# Sheet1.net
KiCad netlist of a schematic drawn in Altium Designer
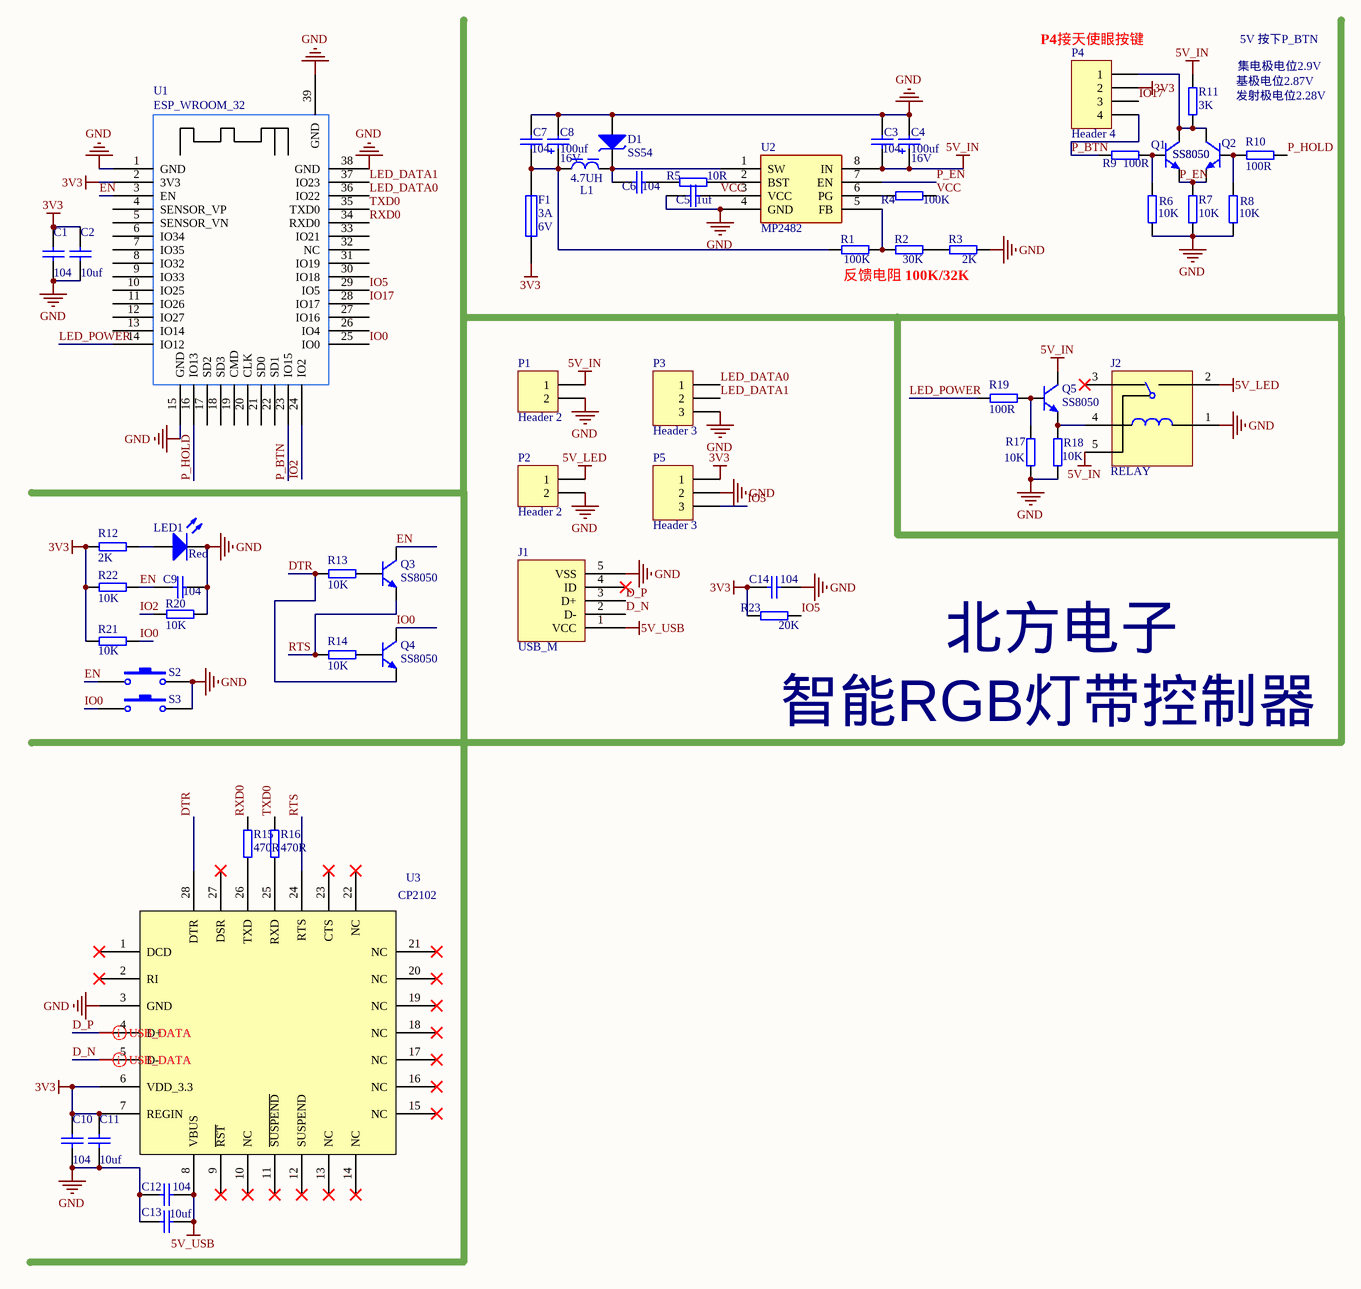
[diagram p0: Sheet1.SchDoc]

(export (version "E")
  (design (tool "Eeschema 10.0.6"))
  (components
    (comp (ref "C1")
      (value "104")
      (footprint "CAPC1005[0402]S")
      (description "Chip Capacitor, Silkscreen Border")
      (fields
        (field (name "VOLTAGE") "63V")
        (field (name "TOLERANCE") "Y5V")
        (field (name "PUBLISHER") "Altium Limited")
      )
      (libsource (lib "!)Miscellaneous Integrated Library") (part "Cap Chip 2"))
    )
    (comp (ref "C2")
      (value "10uf")
      (footprint "CAPC1005[0402]S")
      (description "Chip Capacitor, Silkscreen Border")
      (fields
        (field (name "VOLTAGE") "63V")
        (field (name "TOLERANCE") "Y5V")
        (field (name "PUBLISHER") "Altium Limited")
      )
      (libsource (lib "!)Miscellaneous Integrated Library") (part "Cap Chip 2"))
    )
    (comp (ref "C3")
      (value "104")
      (footprint "CAPC1005[0402]S")
      (description "Chip Capacitor, Silkscreen Border")
      (fields
        (field (name "VOLTAGE") "63V")
        (field (name "TOLERANCE") "Y5V")
        (field (name "PUBLISHER") "Altium Limited")
      )
      (libsource (lib "!)Miscellaneous Integrated Library") (part "Cap Chip 2"))
    )
    (comp (ref "C4")
      (value "100uf")
      (footprint "CAPT6032")
      (description "Molded (Tantalum) Capacitor, 2-Leads,")
      (fields (field (name "VOLTAGE") "16V") (field (name "PUBLISHER") "Altium Limited"))
      (libsource (lib "!)Miscellaneous Integrated Library") (part "Cap Tan"))
    )
    (comp (ref "C5")
      (value "1uf")
      (footprint "CAPC1005[0402]S")
      (description "Chip Capacitor, Silkscreen Border")
      (fields
        (field (name "VOLTAGE") "63V")
        (field (name "TOLERANCE") "Y5V")
        (field (name "PUBLISHER") "Altium Limited")
      )
      (libsource (lib "!)Miscellaneous Integrated Library") (part "Cap Chip 2"))
    )
    (comp (ref "C6")
      (value "104")
      (footprint "CAPC1005[0402]S")
      (description "Chip Capacitor, Silkscreen Border")
      (fields
        (field (name "VOLTAGE") "63V")
        (field (name "TOLERANCE") "Y5V")
        (field (name "PUBLISHER") "Altium Limited")
      )
      (libsource (lib "!)Miscellaneous Integrated Library") (part "Cap Chip 2"))
    )
    (comp (ref "C7")
      (value "104")
      (footprint "CAPC1005[0402]S")
      (description "Chip Capacitor, Silkscreen Border")
      (fields
        (field (name "VOLTAGE") "63V")
        (field (name "TOLERANCE") "Y5V")
        (field (name "PUBLISHER") "Altium Limited")
      )
      (libsource (lib "!)Miscellaneous Integrated Library") (part "Cap Chip 2"))
    )
    (comp (ref "C8")
      (value "100uf")
      (footprint "CAPT6032")
      (description "Molded (Tantalum) Capacitor, 2-Leads,")
      (fields (field (name "VOLTAGE") "16V") (field (name "PUBLISHER") "Altium Limited"))
      (libsource (lib "!)Miscellaneous Integrated Library") (part "Cap Tan"))
    )
    (comp (ref "C9")
      (value "104")
      (footprint "CAPC1005[0402]S")
      (description "Chip Capacitor, Silkscreen Border")
      (fields
        (field (name "VOLTAGE") "63V")
        (field (name "TOLERANCE") "Y5V")
        (field (name "PUBLISHER") "Altium Limited")
      )
      (libsource (lib "!)Miscellaneous Integrated Library") (part "Cap Chip 2"))
    )
    (comp (ref "C10")
      (value "104")
      (footprint "CAPC1005[0402]S")
      (description "Chip Capacitor, Silkscreen Border")
      (fields
        (field (name "VOLTAGE") "63V")
        (field (name "TOLERANCE") "Y5V")
        (field (name "PUBLISHER") "Altium Limited")
      )
      (libsource (lib "!)Miscellaneous Integrated Library") (part "Cap Chip 2"))
    )
    (comp (ref "C11")
      (value "10uf")
      (footprint "CAPC1005[0402]S")
      (description "Chip Capacitor, Silkscreen Border")
      (fields
        (field (name "VOLTAGE") "63V")
        (field (name "TOLERANCE") "Y5V")
        (field (name "PUBLISHER") "Altium Limited")
      )
      (libsource (lib "!)Miscellaneous Integrated Library") (part "Cap Chip 2"))
    )
    (comp (ref "C12")
      (value "104")
      (footprint "CAPC1005[0402]S")
      (description "Chip Capacitor, Silkscreen Border")
      (fields
        (field (name "VOLTAGE") "63V")
        (field (name "TOLERANCE") "Y5V")
        (field (name "PUBLISHER") "Altium Limited")
      )
      (libsource (lib "!)Miscellaneous Integrated Library") (part "Cap Chip 2"))
    )
    (comp (ref "C13")
      (value "10uf")
      (footprint "CAPC1005[0402]S")
      (description "Chip Capacitor, Silkscreen Border")
      (fields
        (field (name "VOLTAGE") "63V")
        (field (name "TOLERANCE") "Y5V")
        (field (name "PUBLISHER") "Altium Limited")
      )
      (libsource (lib "!)Miscellaneous Integrated Library") (part "Cap Chip 2"))
    )
    (comp (ref "C14")
      (value "104")
      (footprint "CAPC1005[0402]S")
      (description "Chip Capacitor, Silkscreen Border")
      (fields
        (field (name "VOLTAGE") "63V")
        (field (name "TOLERANCE") "Y5V")
        (field (name "PUBLISHER") "Altium Limited")
      )
      (libsource (lib "!)Miscellaneous Integrated Library") (part "Cap Chip 2"))
    )
    (comp (ref "D1")
      (value "SS54")
      (footprint "SMA[DO-214AC]")
      (description "TRANSIENT VOLTAGE  SUPPRESSOR DIODE")
      (fields (field (name "PARTNUMBER") "SS54") (field (name "PUBLISHER") "Altium Limited"))
      (libsource (lib "!)Miscellaneous Integrated Library") (part "Diode TVS Uni-Dir"))
    )
    (comp (ref "F1")
      (value "~")
      (footprint "CAPC4532[1812]S")
      (description "Fuse")
      (fields
        (field (name "IMAX") "3A")
        (field (name "VOLTAGE") "6V")
        (field (name "PUBLISHER") "Altium Limited")
      )
      (libsource (lib "!)Miscellaneous Integrated Library") (part "Fuse Chip"))
    )
    (comp (ref "J1")
      (value "USB_M")
      (footprint "1__Micro USB 牛角")
      (description "MicroUSB接口")
      (libsource (lib "Fszhang") (part "USB_M"))
    )
    (comp (ref "J2")
      (value "RELAY")
      (footprint "RELAY-HK3FF")
      (description "单刀双掷继电器")
      (libsource (lib "fszhang") (part "RELAY-HK3FF"))
    )
    (comp (ref "L1")
      (value "4.7UH")
      (footprint "CD75")
      (description "Power Inductor, Ferrite-Core")
      (fields (field (name "PUBLISHER") "Altium Limited"))
      (libsource (lib "!)Miscellaneous Integrated Library") (part "Ind Power"))
    )
    (comp (ref "LED1")
      (value "Red")
      (footprint "LEDC1608(0603)")
      (description "Typical Chip LED")
      (fields (field (name "COLOR") "Red") (field (name "PUBLISHER") "Altium Limited"))
      (libsource (lib "!)Miscellaneous Integrated Library") (part "LED Chip"))
    )
    (comp (ref "P1")
      (value "Header 2")
      (footprint "DC-5.5mm")
      (description "Header, 2-Pin")
      (fields (field (name "PUBLISHER") "Altium Limited"))
      (libsource (lib "!)Miscellaneous Integrated Library") (part "Header 2"))
    )
    (comp (ref "P2")
      (value "Header 2")
      (footprint "KF142R_2P")
      (description "Header, 2-Pin")
      (fields (field (name "PUBLISHER") "Altium Limited"))
      (libsource (lib "!)Miscellaneous Integrated Library") (part "Header 2"))
    )
    (comp (ref "P3")
      (value "Header 3")
      (footprint "HDR1X3")
      (description "Header, 3-Pin")
      (fields (field (name "PUBLISHER") "Altium Limited"))
      (libsource (lib "!)Miscellaneous Integrated Library") (part "Header 3"))
    )
    (comp (ref "P4")
      (value "Header 4")
      (footprint "HDR1X4")
      (description "Header, 4-Pin")
      (fields (field (name "PUBLISHER") "Altium Limited"))
      (libsource (lib "!)Miscellaneous Integrated Library") (part "Header 4"))
    )
    (comp (ref "P5")
      (value "Header 3")
      (footprint "HDR1X3")
      (description "Header, 3-Pin")
      (fields (field (name "PUBLISHER") "Altium Limited"))
      (libsource (lib "!)Miscellaneous Integrated Library") (part "Header 3"))
    )
    (comp (ref "Q1")
      (value "SS8050")
      (footprint "SOT23")
      (description "NPN Bipolar Transistor")
      (fields (field (name "PARTNUMBER") "SS8050") (field (name "PUBLISHER") "Altium Limited"))
      (libsource (lib "!)Miscellaneous Integrated Library") (part "NPN SMC SOT-23"))
    )
    (comp (ref "Q2")
      (value "SS8050")
      (footprint "SOT23")
      (description "NPN Bipolar Transistor")
      (fields (field (name "PARTNUMBER") "SS8050") (field (name "PUBLISHER") "Altium Limited"))
      (libsource (lib "!)Miscellaneous Integrated Library") (part "NPN SMC SOT-23"))
    )
    (comp (ref "Q3")
      (value "SS8050")
      (footprint "SOT23")
      (description "NPN Bipolar Transistor")
      (fields (field (name "PARTNUMBER") "SS8050") (field (name "PUBLISHER") "Altium Limited"))
      (libsource (lib "!)Miscellaneous Integrated Library") (part "NPN SMC SOT-23"))
    )
    (comp (ref "Q4")
      (value "SS8050")
      (footprint "SOT23")
      (description "NPN Bipolar Transistor")
      (fields (field (name "PARTNUMBER") "SS8050") (field (name "PUBLISHER") "Altium Limited"))
      (libsource (lib "!)Miscellaneous Integrated Library") (part "NPN SMC SOT-23"))
    )
    (comp (ref "Q5")
      (value "SS8050")
      (footprint "SOT23")
      (description "NPN Bipolar Transistor")
      (fields (field (name "PARTNUMBER") "SS8050") (field (name "PUBLISHER") "Altium Limited"))
      (libsource (lib "!)Miscellaneous Integrated Library") (part "NPN SMC SOT-23"))
    )
    (comp (ref "R1")
      (value "100K")
      (footprint "RESC1005[0402]S")
      (description "Chip Resistor, Border Silkscreen On PCB Library")
      (fields (field (name "TOLERANCE") "5%") (field (name "PUBLISHER") "Altium Limited"))
      (libsource (lib "!)Miscellaneous Integrated Library") (part "Res Chip 2p 2"))
    )
    (comp (ref "R2")
      (value "30K")
      (footprint "RESC1005[0402]S")
      (description "Chip Resistor, Border Silkscreen On PCB Library")
      (fields (field (name "TOLERANCE") "5%") (field (name "PUBLISHER") "Altium Limited"))
      (libsource (lib "!)Miscellaneous Integrated Library") (part "Res Chip 2p 2"))
    )
    (comp (ref "R3")
      (value "2K")
      (footprint "RESC1005[0402]S")
      (description "Chip Resistor, Border Silkscreen On PCB Library")
      (fields (field (name "TOLERANCE") "5%") (field (name "PUBLISHER") "Altium Limited"))
      (libsource (lib "!)Miscellaneous Integrated Library") (part "Res Chip 2p 2"))
    )
    (comp (ref "R4")
      (value "100K")
      (footprint "RESC1005[0402]S")
      (description "Chip Resistor, Border Silkscreen On PCB Library")
      (fields (field (name "TOLERANCE") "5%") (field (name "PUBLISHER") "Altium Limited"))
      (libsource (lib "!)Miscellaneous Integrated Library") (part "Res Chip 2p 2"))
    )
    (comp (ref "R5")
      (value "10R")
      (footprint "RESC1005[0402]S")
      (description "Chip Resistor, Border Silkscreen On PCB Library")
      (fields (field (name "TOLERANCE") "5%") (field (name "PUBLISHER") "Altium Limited"))
      (libsource (lib "!)Miscellaneous Integrated Library") (part "Res Chip 2p 2"))
    )
    (comp (ref "R6")
      (value "10K")
      (footprint "RESC1005[0402]S")
      (description "Chip Resistor, Border Silkscreen On PCB Library")
      (fields (field (name "TOLERANCE") "5%") (field (name "PUBLISHER") "Altium Limited"))
      (libsource (lib "!)Miscellaneous Integrated Library") (part "Res Chip 2p 2"))
    )
    (comp (ref "R7")
      (value "10K")
      (footprint "RESC1005[0402]S")
      (description "Chip Resistor, Border Silkscreen On PCB Library")
      (fields (field (name "TOLERANCE") "5%") (field (name "PUBLISHER") "Altium Limited"))
      (libsource (lib "!)Miscellaneous Integrated Library") (part "Res Chip 2p 2"))
    )
    (comp (ref "R8")
      (value "10K")
      (footprint "RESC1005[0402]S")
      (description "Chip Resistor, Border Silkscreen On PCB Library")
      (fields (field (name "TOLERANCE") "5%") (field (name "PUBLISHER") "Altium Limited"))
      (libsource (lib "!)Miscellaneous Integrated Library") (part "Res Chip 2p 2"))
    )
    (comp (ref "R9")
      (value "100R")
      (footprint "RESC1005[0402]S")
      (description "Chip Resistor, Border Silkscreen On PCB Library")
      (fields (field (name "TOLERANCE") "5%") (field (name "PUBLISHER") "Altium Limited"))
      (libsource (lib "!)Miscellaneous Integrated Library") (part "Res Chip 2p 2"))
    )
    (comp (ref "R10")
      (value "100R")
      (footprint "RESC1005[0402]S")
      (description "Chip Resistor, Border Silkscreen On PCB Library")
      (fields (field (name "TOLERANCE") "5%") (field (name "PUBLISHER") "Altium Limited"))
      (libsource (lib "!)Miscellaneous Integrated Library") (part "Res Chip 2p 2"))
    )
    (comp (ref "R11")
      (value "3K")
      (footprint "RESC1005[0402]S")
      (description "Chip Resistor, Border Silkscreen On PCB Library")
      (fields (field (name "TOLERANCE") "5%") (field (name "PUBLISHER") "Altium Limited"))
      (libsource (lib "!)Miscellaneous Integrated Library") (part "Res Chip 2p 2"))
    )
    (comp (ref "R12")
      (value "2K")
      (footprint "RESC1005[0402]S")
      (description "Chip Resistor, Border Silkscreen On PCB Library")
      (fields (field (name "TOLERANCE") "5%") (field (name "PUBLISHER") "Altium Limited"))
      (libsource (lib "!)Miscellaneous Integrated Library") (part "Res Chip 2p 2"))
    )
    (comp (ref "R13")
      (value "10K")
      (footprint "RESC1005[0402]S")
      (description "Chip Resistor, Border Silkscreen On PCB Library")
      (fields (field (name "TOLERANCE") "5%") (field (name "PUBLISHER") "Altium Limited"))
      (libsource (lib "!)Miscellaneous Integrated Library") (part "Res Chip 2p 2"))
    )
    (comp (ref "R14")
      (value "10K")
      (footprint "RESC1005[0402]S")
      (description "Chip Resistor, Border Silkscreen On PCB Library")
      (fields (field (name "TOLERANCE") "5%") (field (name "PUBLISHER") "Altium Limited"))
      (libsource (lib "!)Miscellaneous Integrated Library") (part "Res Chip 2p 2"))
    )
    (comp (ref "R15")
      (value "470R")
      (footprint "RESC1005[0402]S")
      (description "Chip Resistor, Border Silkscreen On PCB Library")
      (fields (field (name "TOLERANCE") "5%") (field (name "PUBLISHER") "Altium Limited"))
      (libsource (lib "!)Miscellaneous Integrated Library") (part "Res Chip 2p 2"))
    )
    (comp (ref "R16")
      (value "470R")
      (footprint "RESC1005[0402]S")
      (description "Chip Resistor, Border Silkscreen On PCB Library")
      (fields (field (name "TOLERANCE") "5%") (field (name "PUBLISHER") "Altium Limited"))
      (libsource (lib "!)Miscellaneous Integrated Library") (part "Res Chip 2p 2"))
    )
    (comp (ref "R17")
      (value "10K")
      (footprint "RESC1005[0402]S")
      (description "Chip Resistor, Border Silkscreen On PCB Library")
      (fields (field (name "TOLERANCE") "5%") (field (name "PUBLISHER") "Altium Limited"))
      (libsource (lib "!)Miscellaneous Integrated Library") (part "Res Chip 2p 2"))
    )
    (comp (ref "R18")
      (value "10K")
      (footprint "RESC1005[0402]S")
      (description "Chip Resistor, Border Silkscreen On PCB Library")
      (fields (field (name "TOLERANCE") "5%") (field (name "PUBLISHER") "Altium Limited"))
      (libsource (lib "!)Miscellaneous Integrated Library") (part "Res Chip 2p 2"))
    )
    (comp (ref "R19")
      (value "100R")
      (footprint "RESC1005[0402]S")
      (description "Chip Resistor, Border Silkscreen On PCB Library")
      (fields (field (name "TOLERANCE") "5%") (field (name "PUBLISHER") "Altium Limited"))
      (libsource (lib "!)Miscellaneous Integrated Library") (part "Res Chip 2p 2"))
    )
    (comp (ref "R20")
      (value "10K")
      (footprint "RESC1005[0402]S")
      (description "Chip Resistor, Border Silkscreen On PCB Library")
      (fields (field (name "TOLERANCE") "5%") (field (name "PUBLISHER") "Altium Limited"))
      (libsource (lib "!)Miscellaneous Integrated Library") (part "Res Chip 2p 2"))
    )
    (comp (ref "R21")
      (value "10K")
      (footprint "RESC1005[0402]S")
      (description "Chip Resistor, Border Silkscreen On PCB Library")
      (fields (field (name "TOLERANCE") "5%") (field (name "PUBLISHER") "Altium Limited"))
      (libsource (lib "!)Miscellaneous Integrated Library") (part "Res Chip 2p 2"))
    )
    (comp (ref "R22")
      (value "10K")
      (footprint "RESC1005[0402]S")
      (description "Chip Resistor, Border Silkscreen On PCB Library")
      (fields (field (name "TOLERANCE") "5%") (field (name "PUBLISHER") "Altium Limited"))
      (libsource (lib "!)Miscellaneous Integrated Library") (part "Res Chip 2p 2"))
    )
    (comp (ref "R23")
      (value "20K")
      (footprint "RESC1005[0402]S")
      (description "Chip Resistor, Border Silkscreen On PCB Library")
      (fields (field (name "TOLERANCE") "5%") (field (name "PUBLISHER") "Altium Limited"))
      (libsource (lib "!)Miscellaneous Integrated Library") (part "Res Chip 2p 2"))
    )
    (comp (ref "S2")
      (value "SW-PB")
      (footprint "button")
      (description "Switch")
      (fields (field (name "PUBLISHER") "Altium Limited"))
      (libsource (lib "!)Miscellaneous Integrated Library") (part "SW-PB"))
    )
    (comp (ref "S3")
      (value "SW-PB")
      (footprint "button")
      (description "Switch")
      (fields (field (name "PUBLISHER") "Altium Limited"))
      (libsource (lib "!)Miscellaneous Integrated Library") (part "SW-PB"))
    )
    (comp (ref "U1")
      (value "ESP_WROOM_32")
      (footprint "ESP32")
      (libsource (lib "北方原理图库") (part "ESP_WROOM_32"))
    )
    (comp (ref "U2") (value "MP2482") (footprint "fszhang:SOIC-8") (libsource (lib "北方原理图库") (part "MP2482")))
    (comp (ref "U3") (value "CP2102") (footprint "QFN_28") (libsource (lib "北方原理图库") (part "CP2102")))
  )
  (nets
    (net (code "1") (name "/DTR") (class "Default")
      (node (ref "Q4") (pin "2") (pinfunction "E_2") (pintype "passive"))
      (node (ref "R13") (pin "2") (pinfunction "2_2") (pintype "passive"))
      (node (ref "U3") (pin "28") (pinfunction "DTR_28") (pintype "open_collector"))
    )
    (net (code "2") (name "/D_N") (class "Default")
      (node (ref "J1") (pin "2") (pinfunction "D-_2") (pintype "passive"))
      (node (ref "U3") (pin "5") (pinfunction "D-_5") (pintype "open_collector"))
    )
    (net (code "3") (name "/D_P") (class "Default")
      (node (ref "J1") (pin "3") (pinfunction "D+_3") (pintype "passive"))
      (node (ref "U3") (pin "4") (pinfunction "D+_4") (pintype "open_collector"))
    )
    (net (code "4") (name "/EN") (class "Default")
      (node (ref "C9") (pin "2") (pinfunction "2_2") (pintype "passive"))
      (node (ref "Q3") (pin "3") (pinfunction "C_3") (pintype "passive"))
      (node (ref "R22") (pin "2") (pinfunction "2_2") (pintype "passive"))
      (node (ref "S2") (pin "1") (pinfunction "1_1") (pintype "passive"))
      (node (ref "U1") (pin "3") (pinfunction "EN_3") (pintype "passive"))
    )
    (net (code "5") (name "/IO0") (class "Default")
      (node (ref "Q4") (pin "3") (pinfunction "C_3") (pintype "passive"))
      (node (ref "R21") (pin "2") (pinfunction "2_2") (pintype "passive"))
      (node (ref "S3") (pin "1") (pinfunction "1_1") (pintype "passive"))
      (node (ref "U1") (pin "25") (pinfunction "IO0_25") (pintype "passive"))
    )
    (net (code "6") (name "/IO2") (class "Default")
      (node (ref "R20") (pin "1") (pinfunction "1_1") (pintype "passive"))
      (node (ref "U1") (pin "24") (pinfunction "IO2_24") (pintype "passive"))
    )
    (net (code "7") (name "/IO5") (class "Default")
      (node (ref "P5") (pin "3") (pinfunction "3_3") (pintype "passive"))
      (node (ref "R23") (pin "1") (pinfunction "1_1") (pintype "passive"))
      (node (ref "U1") (pin "29") (pinfunction "IO5_29") (pintype "passive"))
    )
    (net (code "8") (name "/IO17") (class "Default")
      (node (ref "P4") (pin "3") (pinfunction "3_3") (pintype "passive"))
      (node (ref "U1") (pin "28") (pinfunction "IO17_28") (pintype "passive"))
    )
    (net (code "9") (name "/LED_DATA0") (class "Default")
      (node (ref "P3") (pin "1") (pinfunction "1_1") (pintype "passive"))
      (node (ref "U1") (pin "36") (pinfunction "IO22_36") (pintype "passive"))
    )
    (net (code "10") (name "/LED_DATA1") (class "Default")
      (node (ref "P3") (pin "2") (pinfunction "2_2") (pintype "passive"))
      (node (ref "U1") (pin "37") (pinfunction "IO23_37") (pintype "passive"))
    )
    (net (code "11") (name "/LED_POWER") (class "Default")
      (node (ref "R19") (pin "1") (pinfunction "1_1") (pintype "passive"))
      (node (ref "U1") (pin "14") (pinfunction "IO12_14") (pintype "passive"))
    )
    (net (code "12") (name "/P_BTN") (class "Default")
      (node (ref "P4") (pin "4") (pinfunction "4_4") (pintype "passive"))
      (node (ref "R9") (pin "2") (pinfunction "2_2") (pintype "passive"))
      (node (ref "U1") (pin "23") (pinfunction "IO15_23") (pintype "passive"))
    )
    (net (code "13") (name "/P_EN") (class "Default")
      (node (ref "Q1") (pin "2") (pinfunction "E_2") (pintype "passive"))
      (node (ref "Q2") (pin "2") (pinfunction "E_2") (pintype "passive"))
      (node (ref "R7") (pin "2") (pinfunction "2_2") (pintype "passive"))
      (node (ref "U2") (pin "7") (pinfunction "EN_7") (pintype "passive"))
    )
    (net (code "14") (name "/P_HOLD") (class "Default")
      (node (ref "R10") (pin "1") (pinfunction "1_1") (pintype "passive"))
      (node (ref "U1") (pin "16") (pinfunction "IO13_16") (pintype "passive"))
    )
    (net (code "15") (name "/RTS") (class "Default")
      (node (ref "Q3") (pin "2") (pinfunction "E_2") (pintype "passive"))
      (node (ref "R14") (pin "2") (pinfunction "2_2") (pintype "passive"))
      (node (ref "U3") (pin "24") (pinfunction "RTS_24") (pintype "open_collector"))
    )
    (net (code "16") (name "/RXD0") (class "Default")
      (node (ref "R15") (pin "1") (pinfunction "1_1") (pintype "passive"))
      (node (ref "U1") (pin "34") (pinfunction "RXD0_34") (pintype "passive"))
    )
    (net (code "17") (name "/TXD0") (class "Default")
      (node (ref "R16") (pin "1") (pinfunction "1_1") (pintype "passive"))
      (node (ref "U1") (pin "35") (pinfunction "TXD0_35") (pintype "passive"))
    )
    (net (code "18") (name "/VCC") (class "Default")
      (node (ref "C5") (pin "1") (pinfunction "1_1") (pintype "passive"))
      (node (ref "R4") (pin "1") (pinfunction "1_1") (pintype "passive"))
      (node (ref "U2") (pin "3") (pinfunction "VCC_3") (pintype "passive"))
    )
    (net (code "19") (name "3V3") (class "Default")
      (node (ref "C1") (pin "2") (pinfunction "2_2") (pintype "passive"))
      (node (ref "C10") (pin "2") (pinfunction "2_2") (pintype "passive"))
      (node (ref "C11") (pin "2") (pinfunction "2_2") (pintype "passive"))
      (node (ref "C14") (pin "1") (pinfunction "1_1") (pintype "passive"))
      (node (ref "C2") (pin "2") (pinfunction "2_2") (pintype "passive"))
      (node (ref "F1") (pin "1") (pinfunction "1_1") (pintype "passive"))
      (node (ref "P4") (pin "2") (pinfunction "2_2") (pintype "passive"))
      (node (ref "P5") (pin "1") (pinfunction "1_1") (pintype "passive"))
      (node (ref "R12") (pin "1") (pinfunction "1_1") (pintype "passive"))
      (node (ref "R21") (pin "1") (pinfunction "1_1") (pintype "passive"))
      (node (ref "R22") (pin "1") (pinfunction "1_1") (pintype "passive"))
      (node (ref "R23") (pin "2") (pinfunction "2_2") (pintype "passive"))
      (node (ref "U1") (pin "2") (pinfunction "3V3_2") (pintype "passive"))
      (node (ref "U3") (pin "6") (pinfunction "VDD_3.3_6") (pintype "open_collector"))
      (node (ref "U3") (pin "7") (pinfunction "REGIN_7") (pintype "open_collector"))
    )
    (net (code "20") (name "5V_IN") (class "Default")
      (node (ref "C3") (pin "1") (pinfunction "1_1") (pintype "passive"))
      (node (ref "C4") (pin "1") (pinfunction "1_1") (pintype "passive"))
      (node (ref "J2") (pin "5") (pinfunction "5_5") (pintype "passive"))
      (node (ref "P1") (pin "1") (pinfunction "1_1") (pintype "passive"))
      (node (ref "Q5") (pin "3") (pinfunction "C_3") (pintype "passive"))
      (node (ref "R11") (pin "1") (pinfunction "1_1") (pintype "passive"))
      (node (ref "U2") (pin "8") (pinfunction "IN_8") (pintype "passive"))
    )
    (net (code "21") (name "5V_LED") (class "Default")
      (node (ref "J2") (pin "2") (pinfunction "2_2") (pintype "passive"))
      (node (ref "P2") (pin "1") (pinfunction "1_1") (pintype "passive"))
    )
    (net (code "22") (name "5V_USB") (class "Default")
      (node (ref "C12") (pin "2") (pinfunction "2_2") (pintype "passive"))
      (node (ref "C13") (pin "2") (pinfunction "2_2") (pintype "passive"))
      (node (ref "J1") (pin "1") (pinfunction "VCC_1") (pintype "passive"))
      (node (ref "U3") (pin "8") (pinfunction "VBUS_8") (pintype "open_collector"))
    )
    (net (code "23") (name "GND") (class "Default")
      (node (ref "C1") (pin "1") (pinfunction "1_1") (pintype "passive"))
      (node (ref "C10") (pin "1") (pinfunction "1_1") (pintype "passive"))
      (node (ref "C11") (pin "1") (pinfunction "1_1") (pintype "passive"))
      (node (ref "C12") (pin "1") (pinfunction "1_1") (pintype "passive"))
      (node (ref "C13") (pin "1") (pinfunction "1_1") (pintype "passive"))
      (node (ref "C14") (pin "2") (pinfunction "2_2") (pintype "passive"))
      (node (ref "C2") (pin "1") (pinfunction "1_1") (pintype "passive"))
      (node (ref "C3") (pin "2") (pinfunction "2_2") (pintype "passive"))
      (node (ref "C4") (pin "2") (pinfunction "2_2") (pintype "passive"))
      (node (ref "C5") (pin "2") (pinfunction "2_2") (pintype "passive"))
      (node (ref "C7") (pin "2") (pinfunction "2_2") (pintype "passive"))
      (node (ref "C8") (pin "2") (pinfunction "2_2") (pintype "passive"))
      (node (ref "C9") (pin "1") (pinfunction "1_1") (pintype "passive"))
      (node (ref "D1") (pin "A") (pinfunction "A_A") (pintype "passive"))
      (node (ref "J1") (pin "5") (pinfunction "VSS_5") (pintype "passive"))
      (node (ref "J2") (pin "1") (pinfunction "1_1") (pintype "passive"))
      (node (ref "LED1") (pin "C") (pinfunction "C_C") (pintype "passive"))
      (node (ref "P1") (pin "2") (pinfunction "2_2") (pintype "passive"))
      (node (ref "P2") (pin "2") (pinfunction "2_2") (pintype "passive"))
      (node (ref "P3") (pin "3") (pinfunction "3_3") (pintype "passive"))
      (node (ref "P5") (pin "2") (pinfunction "2_2") (pintype "passive"))
      (node (ref "R17") (pin "2") (pinfunction "2_2") (pintype "passive"))
      (node (ref "R18") (pin "2") (pinfunction "2_2") (pintype "passive"))
      (node (ref "R20") (pin "2") (pinfunction "2_2") (pintype "passive"))
      (node (ref "R3") (pin "1") (pinfunction "1_1") (pintype "passive"))
      (node (ref "R6") (pin "1") (pinfunction "1_1") (pintype "passive"))
      (node (ref "R7") (pin "1") (pinfunction "1_1") (pintype "passive"))
      (node (ref "R8") (pin "1") (pinfunction "1_1") (pintype "passive"))
      (node (ref "S2") (pin "2") (pinfunction "2_2") (pintype "passive"))
      (node (ref "S3") (pin "2") (pinfunction "2_2") (pintype "passive"))
      (node (ref "U1") (pin "1") (pinfunction "GND_1") (pintype "passive"))
      (node (ref "U1") (pin "15") (pinfunction "GND_15") (pintype "passive"))
      (node (ref "U1") (pin "38") (pinfunction "GND_38") (pintype "passive"))
      (node (ref "U1") (pin "39") (pinfunction "GND_39") (pintype "passive"))
      (node (ref "U2") (pin "4") (pinfunction "GND_4") (pintype "passive"))
      (node (ref "U3") (pin "3") (pinfunction "GND_3") (pintype "open_collector"))
    )
    (net (code "24") (name "Net-(C6-Pad1)") (class "Default")
      (node (ref "C6") (pin "1") (pinfunction "1_1") (pintype "passive"))
      (node (ref "R5") (pin "2") (pinfunction "2_2") (pintype "passive"))
    )
    (net (code "25") (name "Net-(C7-Pad1)") (class "Default")
      (node (ref "C7") (pin "1") (pinfunction "1_1") (pintype "passive"))
      (node (ref "C8") (pin "1") (pinfunction "1_1") (pintype "passive"))
      (node (ref "F1") (pin "2") (pinfunction "2_2") (pintype "passive"))
      (node (ref "L1") (pin "1") (pinfunction "1_1") (pintype "passive"))
      (node (ref "R1") (pin "2") (pinfunction "2_2") (pintype "passive"))
    )
    (net (code "26") (name "Net-(LED1-PadA)") (class "Default")
      (node (ref "LED1") (pin "A") (pinfunction "A_A") (pintype "passive"))
      (node (ref "R12") (pin "2") (pinfunction "2_2") (pintype "passive"))
    )
    (net (code "27") (name "Net-(Q1-B)") (class "Default")
      (node (ref "Q1") (pin "1") (pinfunction "B_1") (pintype "passive"))
      (node (ref "R6") (pin "2") (pinfunction "2_2") (pintype "passive"))
      (node (ref "R9") (pin "1") (pinfunction "1_1") (pintype "passive"))
    )
    (net (code "28") (name "Net-(Q1-C)") (class "Default")
      (node (ref "P4") (pin "1") (pinfunction "1_1") (pintype "passive"))
      (node (ref "Q1") (pin "3") (pinfunction "C_3") (pintype "passive"))
      (node (ref "Q2") (pin "3") (pinfunction "C_3") (pintype "passive"))
      (node (ref "R11") (pin "2") (pinfunction "2_2") (pintype "passive"))
    )
    (net (code "29") (name "Net-(Q2-B)") (class "Default")
      (node (ref "Q2") (pin "1") (pinfunction "B_1") (pintype "passive"))
      (node (ref "R10") (pin "2") (pinfunction "2_2") (pintype "passive"))
      (node (ref "R8") (pin "2") (pinfunction "2_2") (pintype "passive"))
    )
    (net (code "30") (name "Net-(Q3-B)") (class "Default")
      (node (ref "Q3") (pin "1") (pinfunction "B_1") (pintype "passive"))
      (node (ref "R13") (pin "1") (pinfunction "1_1") (pintype "passive"))
    )
    (net (code "31") (name "Net-(Q4-B)") (class "Default")
      (node (ref "Q4") (pin "1") (pinfunction "B_1") (pintype "passive"))
      (node (ref "R14") (pin "1") (pinfunction "1_1") (pintype "passive"))
    )
    (net (code "32") (name "Net-(Q5-B)") (class "Default")
      (node (ref "Q5") (pin "1") (pinfunction "B_1") (pintype "passive"))
      (node (ref "R17") (pin "1") (pinfunction "1_1") (pintype "passive"))
      (node (ref "R19") (pin "2") (pinfunction "2_2") (pintype "passive"))
    )
    (net (code "33") (name "Net-(Q5-E)") (class "Default")
      (node (ref "J2") (pin "4") (pinfunction "4_4") (pintype "passive"))
      (node (ref "Q5") (pin "2") (pinfunction "E_2") (pintype "passive"))
      (node (ref "R18") (pin "1") (pinfunction "1_1") (pintype "passive"))
    )
    (net (code "34") (name "Net-(R2-Pad1)") (class "Default")
      (node (ref "R2") (pin "1") (pinfunction "1_1") (pintype "passive"))
      (node (ref "R3") (pin "2") (pinfunction "2_2") (pintype "passive"))
    )
    (net (code "35") (name "Net-(U2-BST)") (class "Default")
      (node (ref "R5") (pin "1") (pinfunction "1_1") (pintype "passive"))
      (node (ref "U2") (pin "2") (pinfunction "BST_2") (pintype "passive"))
    )
    (net (code "36") (name "Net-(U2-FB)") (class "Default")
      (node (ref "R1") (pin "1") (pinfunction "1_1") (pintype "passive"))
      (node (ref "R2") (pin "2") (pinfunction "2_2") (pintype "passive"))
      (node (ref "U2") (pin "5") (pinfunction "FB_5") (pintype "passive"))
    )
    (net (code "37") (name "Net-(U2-PG)") (class "Default")
      (node (ref "R4") (pin "2") (pinfunction "2_2") (pintype "passive"))
      (node (ref "U2") (pin "6") (pinfunction "PG_6") (pintype "passive"))
    )
    (net (code "38") (name "Net-(U2-SW)") (class "Default")
      (node (ref "C6") (pin "2") (pinfunction "2_2") (pintype "passive"))
      (node (ref "D1") (pin "K") (pinfunction "K_K") (pintype "passive"))
      (node (ref "L1") (pin "2") (pinfunction "2_2") (pintype "passive"))
      (node (ref "U2") (pin "1") (pinfunction "SW_1") (pintype "passive"))
    )
    (net (code "39") (name "Net-(U3-RXD)") (class "Default")
      (node (ref "R16") (pin "2") (pinfunction "2_2") (pintype "passive"))
      (node (ref "U3") (pin "25") (pinfunction "RXD_25") (pintype "open_collector"))
    )
    (net (code "40") (name "Net-(U3-TXD)") (class "Default")
      (node (ref "R15") (pin "2") (pinfunction "2_2") (pintype "passive"))
      (node (ref "U3") (pin "26") (pinfunction "TXD_26") (pintype "open_collector"))
    )
    (net (code "41") (name "unconnected-(J1-ID-Pad4)") (class "Default")
      (node (ref "J1") (pin "4") (pinfunction "ID_4") (pintype "passive+no_connect"))
    )
    (net (code "42") (name "unconnected-(J2-Pad3)") (class "Default")
      (node (ref "J2") (pin "3") (pinfunction "3_3") (pintype "passive+no_connect"))
    )
    (net (code "43") (name "unconnected-(U1-CLK-Pad20)") (class "Default")
      (node (ref "U1") (pin "20") (pinfunction "CLK_20") (pintype "passive"))
    )
    (net (code "44") (name "unconnected-(U1-CMD-Pad19)") (class "Default")
      (node (ref "U1") (pin "19") (pinfunction "CMD_19") (pintype "passive"))
    )
    (net (code "45") (name "unconnected-(U1-IO4-Pad26)") (class "Default")
      (node (ref "U1") (pin "26") (pinfunction "IO4_26") (pintype "passive"))
    )
    (net (code "46") (name "unconnected-(U1-IO14-Pad13)") (class "Default")
      (node (ref "U1") (pin "13") (pinfunction "IO14_13") (pintype "passive"))
    )
    (net (code "47") (name "unconnected-(U1-IO16-Pad27)") (class "Default")
      (node (ref "U1") (pin "27") (pinfunction "IO16_27") (pintype "passive"))
    )
    (net (code "48") (name "unconnected-(U1-IO18-Pad30)") (class "Default")
      (node (ref "U1") (pin "30") (pinfunction "IO18_30") (pintype "passive"))
    )
    (net (code "49") (name "unconnected-(U1-IO19-Pad31)") (class "Default")
      (node (ref "U1") (pin "31") (pinfunction "IO19_31") (pintype "passive"))
    )
    (net (code "50") (name "unconnected-(U1-IO21-Pad33)") (class "Default")
      (node (ref "U1") (pin "33") (pinfunction "IO21_33") (pintype "passive"))
    )
    (net (code "51") (name "unconnected-(U1-IO25-Pad10)") (class "Default")
      (node (ref "U1") (pin "10") (pinfunction "IO25_10") (pintype "passive"))
    )
    (net (code "52") (name "unconnected-(U1-IO26-Pad11)") (class "Default")
      (node (ref "U1") (pin "11") (pinfunction "IO26_11") (pintype "passive"))
    )
    (net (code "53") (name "unconnected-(U1-IO27-Pad12)") (class "Default")
      (node (ref "U1") (pin "12") (pinfunction "IO27_12") (pintype "passive"))
    )
    (net (code "54") (name "unconnected-(U1-IO32-Pad8)") (class "Default")
      (node (ref "U1") (pin "8") (pinfunction "IO32_8") (pintype "passive"))
    )
    (net (code "55") (name "unconnected-(U1-IO33-Pad9)") (class "Default")
      (node (ref "U1") (pin "9") (pinfunction "IO33_9") (pintype "passive"))
    )
    (net (code "56") (name "unconnected-(U1-IO34-Pad6)") (class "Default")
      (node (ref "U1") (pin "6") (pinfunction "IO34_6") (pintype "passive"))
    )
    (net (code "57") (name "unconnected-(U1-IO35-Pad7)") (class "Default")
      (node (ref "U1") (pin "7") (pinfunction "IO35_7") (pintype "passive"))
    )
    (net (code "58") (name "unconnected-(U1-NC-Pad32)") (class "Default")
      (node (ref "U1") (pin "32") (pinfunction "NC_32") (pintype "passive"))
    )
    (net (code "59") (name "unconnected-(U1-SD0-Pad21)") (class "Default")
      (node (ref "U1") (pin "21") (pinfunction "SD0_21") (pintype "passive"))
    )
    (net (code "60") (name "unconnected-(U1-SD1-Pad22)") (class "Default")
      (node (ref "U1") (pin "22") (pinfunction "SD1_22") (pintype "passive"))
    )
    (net (code "61") (name "unconnected-(U1-SD2-Pad17)") (class "Default")
      (node (ref "U1") (pin "17") (pinfunction "SD2_17") (pintype "passive"))
    )
    (net (code "62") (name "unconnected-(U1-SD3-Pad18)") (class "Default")
      (node (ref "U1") (pin "18") (pinfunction "SD3_18") (pintype "passive"))
    )
    (net (code "63") (name "unconnected-(U1-SENSOR_VN-Pad5)") (class "Default")
      (node (ref "U1") (pin "5") (pinfunction "SENSOR_VN_5") (pintype "passive"))
    )
    (net (code "64") (name "unconnected-(U1-SENSOR_VP-Pad4)") (class "Default")
      (node (ref "U1") (pin "4") (pinfunction "SENSOR_VP_4") (pintype "passive"))
    )
    (net (code "65") (name "unconnected-(U3-CTS-Pad23)") (class "Default")
      (node (ref "U3") (pin "23") (pinfunction "CTS_23") (pintype "open_collector+no_connect"))
    )
    (net (code "66") (name "unconnected-(U3-DCD-Pad1)") (class "Default")
      (node (ref "U3") (pin "1") (pinfunction "DCD_1") (pintype "open_collector+no_connect"))
    )
    (net (code "67") (name "unconnected-(U3-DSR-Pad27)") (class "Default")
      (node (ref "U3") (pin "27") (pinfunction "DSR_27") (pintype "open_collector+no_connect"))
    )
    (net (code "68") (name "unconnected-(U3-NC-Pad10)") (class "Default")
      (node (ref "U3") (pin "10") (pinfunction "NC_10") (pintype "open_collector+no_connect"))
    )
    (net (code "69") (name "unconnected-(U3-NC-Pad13)") (class "Default")
      (node (ref "U3") (pin "13") (pinfunction "NC_13") (pintype "open_collector+no_connect"))
    )
    (net (code "70") (name "unconnected-(U3-NC-Pad14)") (class "Default")
      (node (ref "U3") (pin "14") (pinfunction "NC_14") (pintype "open_collector+no_connect"))
    )
    (net (code "71") (name "unconnected-(U3-NC-Pad15)") (class "Default")
      (node (ref "U3") (pin "15") (pinfunction "NC_15") (pintype "open_collector+no_connect"))
    )
    (net (code "72") (name "unconnected-(U3-NC-Pad16)") (class "Default")
      (node (ref "U3") (pin "16") (pinfunction "NC_16") (pintype "open_collector+no_connect"))
    )
    (net (code "73") (name "unconnected-(U3-NC-Pad17)") (class "Default")
      (node (ref "U3") (pin "17") (pinfunction "NC_17") (pintype "open_collector+no_connect"))
    )
    (net (code "74") (name "unconnected-(U3-NC-Pad18)") (class "Default")
      (node (ref "U3") (pin "18") (pinfunction "NC_18") (pintype "open_collector+no_connect"))
    )
    (net (code "75") (name "unconnected-(U3-NC-Pad19)") (class "Default")
      (node (ref "U3") (pin "19") (pinfunction "NC_19") (pintype "open_collector+no_connect"))
    )
    (net (code "76") (name "unconnected-(U3-NC-Pad20)") (class "Default")
      (node (ref "U3") (pin "20") (pinfunction "NC_20") (pintype "open_collector+no_connect"))
    )
    (net (code "77") (name "unconnected-(U3-NC-Pad21)") (class "Default")
      (node (ref "U3") (pin "21") (pinfunction "NC_21") (pintype "open_collector+no_connect"))
    )
    (net (code "78") (name "unconnected-(U3-NC-Pad22)") (class "Default")
      (node (ref "U3") (pin "22") (pinfunction "NC_22") (pintype "open_collector+no_connect"))
    )
    (net (code "79") (name "unconnected-(U3-RI-Pad2)") (class "Default")
      (node (ref "U3") (pin "2") (pinfunction "RI_2") (pintype "open_collector+no_connect"))
    )
    (net (code "80") (name "unconnected-(U3-SUSPEND-Pad12)") (class "Default")
      (node (ref "U3") (pin "12") (pinfunction "SUSPEND_12") (pintype "open_collector+no_connect"))
    )
    (net (code "81") (name "unconnected-(U3-~{RST}-Pad9)") (class "Default")
      (node (ref "U3") (pin "9") (pinfunction "~{RST}_9") (pintype "open_collector+no_connect"))
    )
    (net (code "82") (name "unconnected-(U3-~{SUSPEND}-Pad11)") (class "Default")
      (node (ref "U3") (pin "11") (pinfunction "~{SUSPEND}_11") (pintype "open_collector+no_connect"))
    )
  )
)
